# CNC_Power_V2.net
KiCad netlist of a schematic drawn in EAGLE
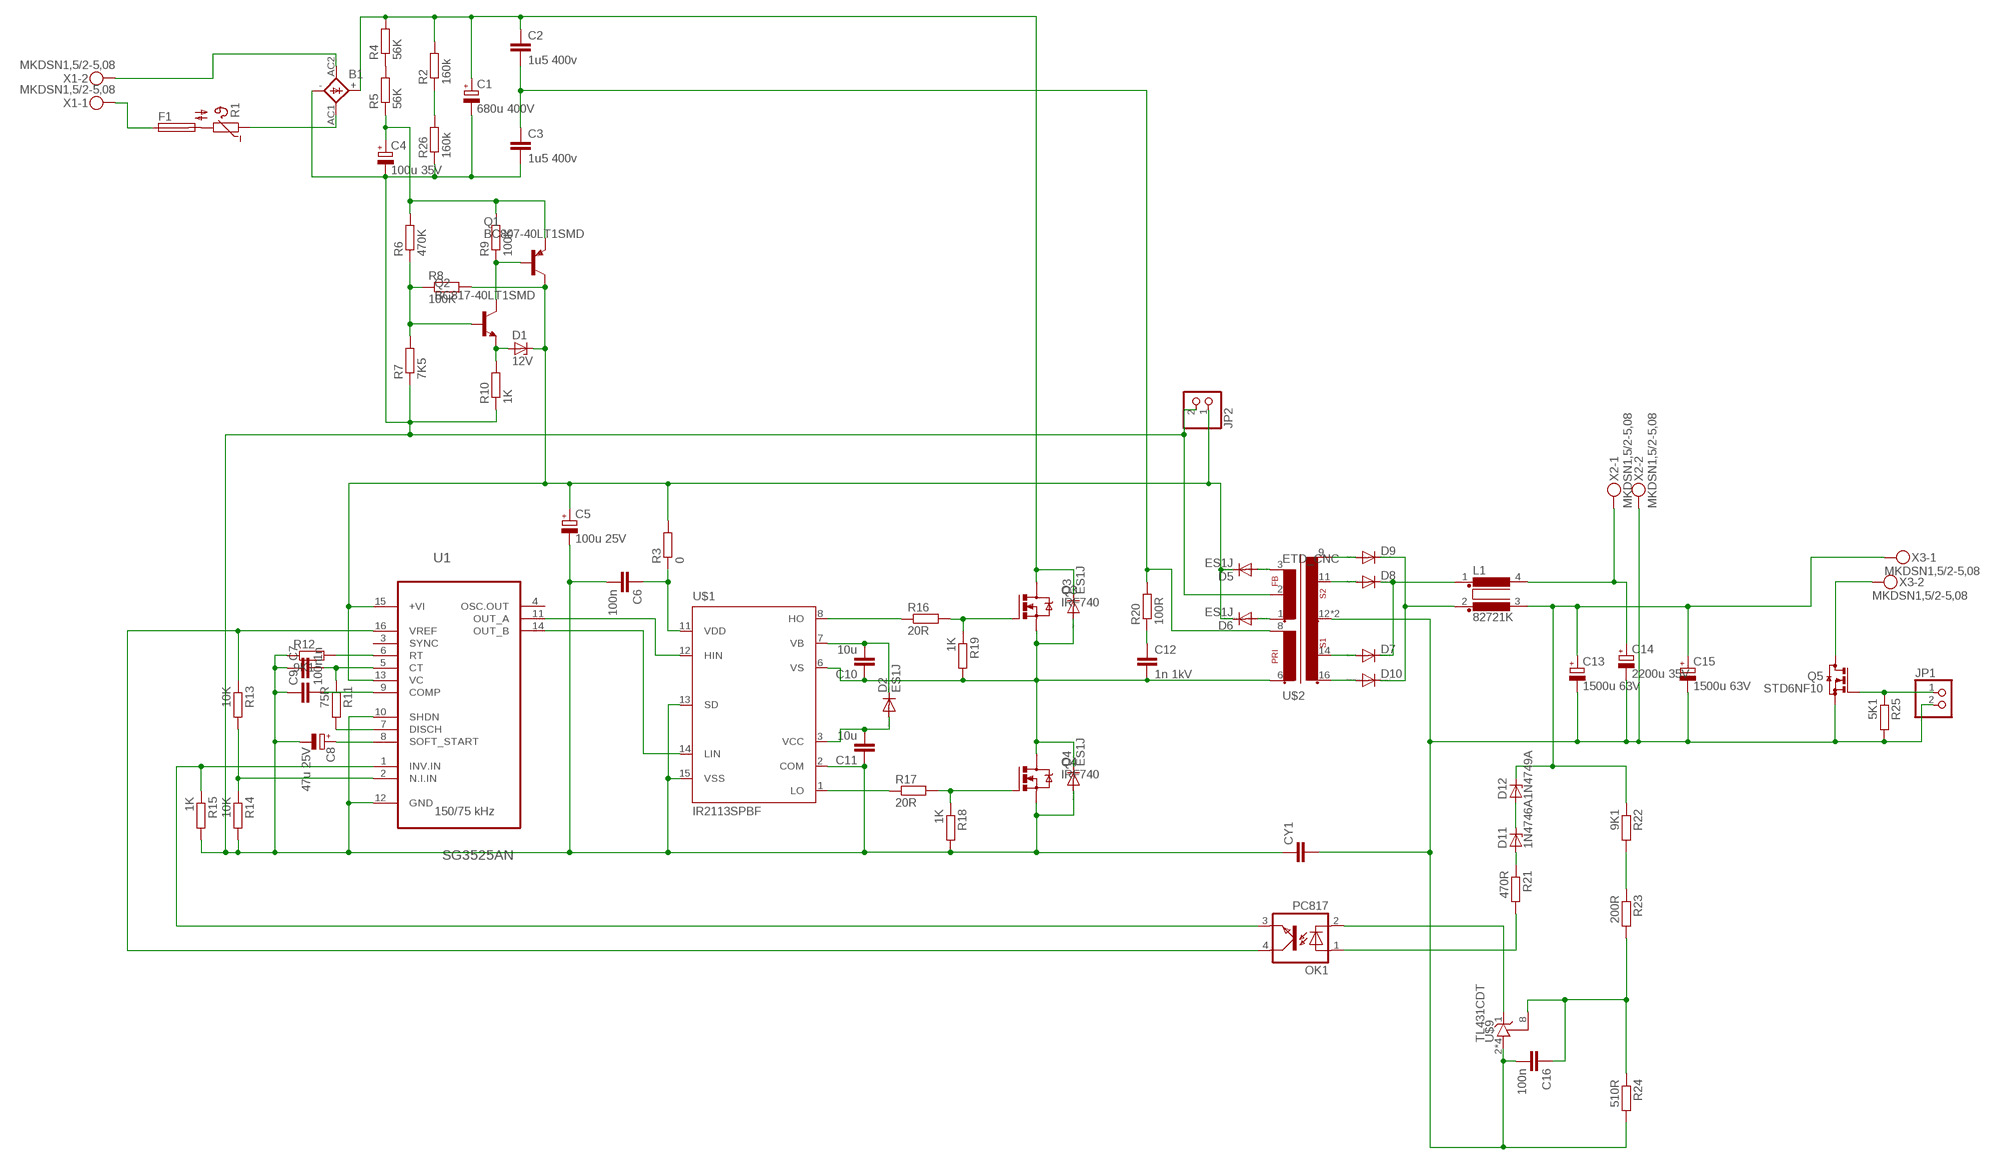
[diagram p0: schematic, sheet 1]

(export (version "E")
  (design (tool "Eeschema 10.0.6"))
  (components
    (comp (ref "B1")
      (value "KBL")
      (footprint "eagle-import:KBL")
      (libsource (lib "eagle-import") (part "KBL"))
    )
    (comp (ref "C1")
      (value "680u 400V")
      (footprint "eagle-import:EB35D")
      (libsource (lib "eagle-import") (part "CPOL-EUE10-35"))
    )
    (comp (ref "C2")
      (value "1u5 400v")
      (footprint "eagle-import:C225-074X268")
      (libsource (lib "eagle-import") (part "C-EU225-074X268"))
    )
    (comp (ref "C3")
      (value "1u5 400v")
      (footprint "eagle-import:C225-074X268")
      (libsource (lib "eagle-import") (part "C-EU225-074X268"))
    )
    (comp (ref "C4")
      (value "100u 35V")
      (footprint "eagle-import:E2,5-7")
      (libsource (lib "eagle-import") (part "CPOL-EUE2.5-7"))
    )
    (comp (ref "C5")
      (value "100u 25V")
      (footprint "eagle-import:E2,5-7")
      (libsource (lib "eagle-import") (part "CPOL-EUE2.5-7"))
    )
    (comp (ref "C6")
      (value "100n")
      (footprint "eagle-import:C0805")
      (libsource (lib "eagle-import") (part "C-EUC0805"))
    )
    (comp (ref "C7")
      (value "1n")
      (footprint "eagle-import:C0805")
      (libsource (lib "eagle-import") (part "C-EUC0805"))
    )
    (comp (ref "C8")
      (value "47u 25V")
      (footprint "eagle-import:E2,5-7")
      (libsource (lib "eagle-import") (part "CPOL-EUE2.5-7"))
    )
    (comp (ref "C9")
      (value "100n")
      (footprint "eagle-import:C0805")
      (libsource (lib "eagle-import") (part "C-EUC0805"))
    )
    (comp (ref "C10")
      (value "10u")
      (footprint "eagle-import:C0805")
      (libsource (lib "eagle-import") (part "C-EUC0805"))
    )
    (comp (ref "C11")
      (value "10u")
      (footprint "eagle-import:C0805")
      (libsource (lib "eagle-import") (part "C-EUC0805"))
    )
    (comp (ref "C12")
      (value "1n 1kV")
      (footprint "eagle-import:C050-025X075")
      (libsource (lib "eagle-import") (part "C-EU050-025X075"))
    )
    (comp (ref "C13")
      (value "1500u 63V")
      (footprint "eagle-import:E7,5-18")
      (libsource (lib "eagle-import") (part "CPOL-EUE7.5-18"))
    )
    (comp (ref "C14")
      (value "2200u 35V")
      (footprint "eagle-import:E7,5-18")
      (libsource (lib "eagle-import") (part "CPOL-EUE7.5-18"))
    )
    (comp (ref "C15")
      (value "1500u 63V")
      (footprint "eagle-import:E7,5-18")
      (libsource (lib "eagle-import") (part "CPOL-EUE7.5-18"))
    )
    (comp (ref "C16")
      (value "100n")
      (footprint "eagle-import:C0805")
      (libsource (lib "eagle-import") (part "C-EUC0805"))
    )
    (comp (ref "CY1")
      (value "CYYC10B4")
      (footprint "eagle-import:YC10B4")
      (libsource (lib "eagle-import") (part "CYYC10B4"))
    )
    (comp (ref "D1")
      (value "12V")
      (footprint "eagle-import:SOD80C")
      (libsource (lib "eagle-import") (part "ZENER-DIODESOD80C"))
    )
    (comp (ref "D2")
      (value "ES1J")
      (footprint "eagle-import:DO214AC")
      (libsource (lib "eagle-import") (part "DIODE-DO214AC"))
    )
    (comp (ref "D3")
      (value "ES1J")
      (footprint "eagle-import:DO214AC")
      (libsource (lib "eagle-import") (part "DIODE-DO214AC"))
    )
    (comp (ref "D4")
      (value "ES1J")
      (footprint "eagle-import:DO214AC")
      (libsource (lib "eagle-import") (part "DIODE-DO214AC"))
    )
    (comp (ref "D5")
      (value "ES1J")
      (footprint "eagle-import:DO214AC")
      (libsource (lib "eagle-import") (part "DIODE-DO214AC"))
    )
    (comp (ref "D6")
      (value "ES1J")
      (footprint "eagle-import:DO214AC")
      (libsource (lib "eagle-import") (part "DIODE-DO214AC"))
    )
    (comp (ref "D7")
      (value "DIODE-DO220S")
      (footprint "eagle-import:DO220S")
      (libsource (lib "eagle-import") (part "DIODE-DO220S"))
    )
    (comp (ref "D8")
      (value "DIODE-DO220S")
      (footprint "eagle-import:DO220S")
      (libsource (lib "eagle-import") (part "DIODE-DO220S"))
    )
    (comp (ref "D9")
      (value "DIODE-DO220S")
      (footprint "eagle-import:DO220S")
      (libsource (lib "eagle-import") (part "DIODE-DO220S"))
    )
    (comp (ref "D10")
      (value "DIODE-DO220S")
      (footprint "eagle-import:DO220S")
      (libsource (lib "eagle-import") (part "DIODE-DO220S"))
    )
    (comp (ref "D11")
      (value "1N4746A")
      (footprint "eagle-import:DO41Z10")
      (libsource (lib "eagle-import") (part "ZENER-DIODEDO41Z10"))
    )
    (comp (ref "D12")
      (value "1N4749A")
      (footprint "eagle-import:DO41Z10")
      (libsource (lib "eagle-import") (part "ZENER-DIODEDO41Z10"))
    )
    (comp (ref "F1")
      (value "SH22,5")
      (footprint "eagle-import:SH22,5")
      (fields (field (name "MF") "SCHURTER") (field (name "MPN") "0031.8201"))
      (libsource (lib "eagle-import") (part "SH22,5"))
    )
    (comp (ref "JP1")
      (value "PINHD-1X2")
      (footprint "eagle-import:1X02")
      (libsource (lib "eagle-import") (part "PINHD-1X2"))
    )
    (comp (ref "JP2")
      (value "PINHD-1X2")
      (footprint "eagle-import:1X02")
      (libsource (lib "eagle-import") (part "PINHD-1X2"))
    )
    (comp (ref "L1")
      (value "82721K")
      (footprint "eagle-import:82721K")
      (libsource (lib "eagle-import") (part "82721K"))
    )
    (comp (ref "OK1")
      (value "PC817")
      (footprint "eagle-import:DIL04")
      (fields (field (name "MPN") "PC817X4J000F"))
      (libsource (lib "eagle-import") (part "PC817"))
    )
    (comp (ref "Q1")
      (value "BC807-40LT1SMD")
      (footprint "eagle-import:SOT23-BEC")
      (libsource (lib "eagle-import") (part "BC807SMD-40LT1"))
    )
    (comp (ref "Q2")
      (value "BC817-40LT1SMD")
      (footprint "eagle-import:SOT23-BEC")
      (libsource (lib "eagle-import") (part "BC817SMD-40LT1"))
    )
    (comp (ref "Q3")
      (value "IRF740")
      (footprint "eagle-import:TO220BV")
      (libsource (lib "eagle-import") (part "IRF740"))
    )
    (comp (ref "Q4")
      (value "IRF740")
      (footprint "eagle-import:TO220BV")
      (libsource (lib "eagle-import") (part "IRF740"))
    )
    (comp (ref "Q5")
      (value "STD6NF10")
      (footprint "eagle-import:DPAK")
      (libsource (lib "eagle-import") (part "STD6NF10"))
    )
    (comp (ref "R1")
      (value "B57164")
      (footprint "eagle-import:B57164")
      (fields (field (name "MPN") "B57164K474K52"))
      (libsource (lib "eagle-import") (part "B57164"))
    )
    (comp (ref "R2")
      (value "160k")
      (footprint "eagle-import:0207_10")
      (libsource (lib "eagle-import") (part "R-EU_0207/10"))
    )
    (comp (ref "R3")
      (value "0")
      (footprint "eagle-import:R1206")
      (libsource (lib "eagle-import") (part "R-EU_R1206"))
    )
    (comp (ref "R4")
      (value "56K")
      (footprint "eagle-import:0617_17")
      (libsource (lib "eagle-import") (part "R-EU_0617/17"))
    )
    (comp (ref "R5")
      (value "56K")
      (footprint "eagle-import:0617_17")
      (libsource (lib "eagle-import") (part "R-EU_0617/17"))
    )
    (comp (ref "R6")
      (value "470K")
      (footprint "eagle-import:R0805")
      (libsource (lib "eagle-import") (part "R-EU_R0805"))
    )
    (comp (ref "R7")
      (value "7K5")
      (footprint "eagle-import:R0805")
      (libsource (lib "eagle-import") (part "R-EU_R0805"))
    )
    (comp (ref "R8")
      (value "100K")
      (footprint "eagle-import:R0805")
      (libsource (lib "eagle-import") (part "R-EU_R0805"))
    )
    (comp (ref "R9")
      (value "100K")
      (footprint "eagle-import:R0805")
      (libsource (lib "eagle-import") (part "R-EU_R0805"))
    )
    (comp (ref "R10")
      (value "1K")
      (footprint "eagle-import:R0805")
      (libsource (lib "eagle-import") (part "R-EU_R0805"))
    )
    (comp (ref "R11")
      (value "75R")
      (footprint "eagle-import:R0805")
      (libsource (lib "eagle-import") (part "R-EU_R0805"))
    )
    (comp (ref "R12")
      (value "9K1")
      (footprint "eagle-import:R0805")
      (libsource (lib "eagle-import") (part "R-EU_R0805"))
    )
    (comp (ref "R13")
      (value "10K")
      (footprint "eagle-import:R0805")
      (libsource (lib "eagle-import") (part "R-EU_R0805"))
    )
    (comp (ref "R14")
      (value "10K")
      (footprint "eagle-import:R0805")
      (libsource (lib "eagle-import") (part "R-EU_R0805"))
    )
    (comp (ref "R15")
      (value "1K")
      (footprint "eagle-import:R0805")
      (libsource (lib "eagle-import") (part "R-EU_R0805"))
    )
    (comp (ref "R16")
      (value "20R")
      (footprint "eagle-import:R1206")
      (libsource (lib "eagle-import") (part "R-EU_R1206"))
    )
    (comp (ref "R17")
      (value "20R")
      (footprint "eagle-import:R1206")
      (libsource (lib "eagle-import") (part "R-EU_R1206"))
    )
    (comp (ref "R18")
      (value "1K")
      (footprint "eagle-import:R0805")
      (libsource (lib "eagle-import") (part "R-EU_R0805"))
    )
    (comp (ref "R19")
      (value "1K")
      (footprint "eagle-import:R0805")
      (libsource (lib "eagle-import") (part "R-EU_R0805"))
    )
    (comp (ref "R20")
      (value "100R")
      (footprint "eagle-import:0617_17")
      (libsource (lib "eagle-import") (part "R-EU_0617/17"))
    )
    (comp (ref "R21")
      (value "470R")
      (footprint "eagle-import:R0805")
      (libsource (lib "eagle-import") (part "R-EU_R0805"))
    )
    (comp (ref "R22")
      (value "9K1")
      (footprint "eagle-import:R0805")
      (libsource (lib "eagle-import") (part "R-EU_R0805"))
    )
    (comp (ref "R23")
      (value "200R")
      (footprint "eagle-import:R0805")
      (libsource (lib "eagle-import") (part "R-EU_R0805"))
    )
    (comp (ref "R24")
      (value "510R")
      (footprint "eagle-import:R0805")
      (libsource (lib "eagle-import") (part "R-EU_R0805"))
    )
    (comp (ref "R25")
      (value "5K1")
      (footprint "eagle-import:R0805")
      (libsource (lib "eagle-import") (part "R-EU_R0805"))
    )
    (comp (ref "R26")
      (value "160k")
      (footprint "eagle-import:0207_10")
      (libsource (lib "eagle-import") (part "R-EU_0207/10"))
    )
    (comp (ref "U$1")
      (value "IR2113SPBF")
      (footprint "eagle-import:SO16W")
      (libsource (lib "eagle-import") (part "IR2113SPBF"))
    )
    (comp (ref "U$2")
      (value "ETD_CNC")
      (footprint "eagle-import:ETD39_16PIN")
      (libsource (lib "eagle-import") (part "ETD_CNC"))
    )
    (comp (ref "U$9")
      (value "TL431CDT")
      (footprint "eagle-import:SO8")
      (libsource (lib "eagle-import") (part "TL431CDT"))
    )
    (comp (ref "U1")
      (value "SG3525AN")
      (footprint "eagle-import:DIP254P762X510-16")
      (libsource (lib "eagle-import") (part "SG3525AN"))
    )
    (comp (ref "X1")
      (value "MKDSN1,5/2-5,08")
      (footprint "eagle-import:MKDSN1,5_2-5,08")
      (libsource (lib "eagle-import") (part "MKDSN1,5/2-5,08"))
    )
    (comp (ref "X2")
      (value "MKDSN1,5/2-5,08")
      (footprint "eagle-import:MKDSN1,5_2-5,08")
      (libsource (lib "eagle-import") (part "MKDSN1,5/2-5,08"))
    )
    (comp (ref "X3")
      (value "MKDSN1,5/2-5,08")
      (footprint "eagle-import:MKDSN1,5_2-5,08")
      (libsource (lib "eagle-import") (part "MKDSN1,5/2-5,08"))
    )
  )
  (nets
    (net (code "1") (name "Net-(B1-AC1)") (class "Default")
      (node (ref "B1") (pin "AC2") (pinfunction "AC1_AC2") (pintype "passive"))
      (node (ref "X1") (pin "2") (pinfunction "KL_2") (pintype "passive"))
    )
    (net (code "2") (name "Net-(B1-AC2)") (class "Default")
      (node (ref "B1") (pin "AC1") (pinfunction "AC2_AC1") (pintype "passive"))
      (node (ref "R1") (pin "1") (pinfunction "1_1") (pintype "passive"))
    )
    (net (code "3") (name "Net-(B1-Pad+)") (class "Default")
      (node (ref "B1") (pin "+") (pinfunction "+_+") (pintype "passive"))
      (node (ref "C1") (pin "+") (pinfunction "+_+") (pintype "passive"))
      (node (ref "C2") (pin "1") (pinfunction "1_1") (pintype "passive"))
      (node (ref "D3") (pin "C") (pinfunction "C_C") (pintype "passive"))
      (node (ref "Q3") (pin "D") (pinfunction "D_D") (pintype "passive"))
      (node (ref "R2") (pin "2") (pinfunction "2_2") (pintype "passive"))
      (node (ref "R4") (pin "2") (pinfunction "2_2") (pintype "passive"))
    )
    (net (code "4") (name "Net-(C4-Pad+)") (class "Default")
      (node (ref "C4") (pin "+") (pinfunction "+_+") (pintype "passive"))
      (node (ref "Q1") (pin "E") (pinfunction "E_E") (pintype "passive"))
      (node (ref "R5") (pin "1") (pinfunction "1_1") (pintype "passive"))
      (node (ref "R6") (pin "2") (pinfunction "2_2") (pintype "passive"))
      (node (ref "R9") (pin "2") (pinfunction "2_2") (pintype "passive"))
    )
    (net (code "5") (name "Net-(C12-Pad1)") (class "Default")
      (node (ref "C12") (pin "1") (pinfunction "1_1") (pintype "passive"))
      (node (ref "R20") (pin "1") (pinfunction "1_1") (pintype "passive"))
    )
    (net (code "6") (name "Net-(D1-PadA)") (class "Default")
      (node (ref "D1") (pin "A") (pinfunction "A_A") (pintype "passive"))
      (node (ref "Q2") (pin "E") (pinfunction "E_E") (pintype "passive"))
      (node (ref "R10") (pin "2") (pinfunction "2_2") (pintype "passive"))
    )
    (net (code "7") (name "Net-(D7-PadC)") (class "Default")
      (node (ref "D7") (pin "C") (pinfunction "C_C") (pintype "passive"))
      (node (ref "D8") (pin "C") (pinfunction "C_C") (pintype "passive"))
      (node (ref "L1") (pin "1") (pinfunction "1_1") (pintype "passive"))
    )
    (net (code "8") (name "Net-(D11-PadA)") (class "Default")
      (node (ref "D11") (pin "A") (pinfunction "A_A") (pintype "passive"))
      (node (ref "R21") (pin "1") (pinfunction "1_1") (pintype "passive"))
    )
    (net (code "9") (name "Net-(D11-PadC)") (class "Default")
      (node (ref "D11") (pin "C") (pinfunction "C_C") (pintype "passive"))
      (node (ref "D12") (pin "A") (pinfunction "A_A") (pintype "passive"))
    )
    (net (code "10") (name "Net-(F1-Pad2)") (class "Default")
      (node (ref "F1") (pin "2") (pinfunction "2_2") (pintype "passive"))
      (node (ref "R1") (pin "2") (pinfunction "2_2") (pintype "passive"))
    )
    (net (code "11") (name "Net-(JP1-Pad1)") (class "Default")
      (node (ref "JP1") (pin "1") (pinfunction "1_1") (pintype "passive"))
      (node (ref "Q5") (pin "G") (pinfunction "G_G") (pintype "passive"))
      (node (ref "R25") (pin "1") (pinfunction "1_1") (pintype "passive"))
    )
    (net (code "12") (name "Net-(L1-2)") (class "Default")
      (node (ref "C14") (pin "+") (pinfunction "+_+") (pintype "passive"))
      (node (ref "L1") (pin "4") (pinfunction "2_4") (pintype "passive"))
      (node (ref "X2") (pin "1") (pinfunction "KL_1") (pintype "passive"))
    )
    (net (code "13") (name "Net-(L1-3)") (class "Default")
      (node (ref "D10") (pin "C") (pinfunction "C_C") (pintype "passive"))
      (node (ref "D9") (pin "C") (pinfunction "C_C") (pintype "passive"))
      (node (ref "L1") (pin "2") (pinfunction "3_2") (pintype "passive"))
    )
    (net (code "14") (name "Net-(L1-4)") (class "Default")
      (node (ref "C13") (pin "+") (pinfunction "+_+") (pintype "passive"))
      (node (ref "C15") (pin "+") (pinfunction "+_+") (pintype "passive"))
      (node (ref "D12") (pin "C") (pinfunction "C_C") (pintype "passive"))
      (node (ref "L1") (pin "3") (pinfunction "4_3") (pintype "passive"))
      (node (ref "R22") (pin "1") (pinfunction "1_1") (pintype "passive"))
      (node (ref "X3") (pin "1") (pinfunction "KL_1") (pintype "passive"))
    )
    (net (code "15") (name "Net-(OK1-A)") (class "Default")
      (node (ref "OK1") (pin "1") (pinfunction "A_1") (pintype "passive"))
      (node (ref "R21") (pin "2") (pinfunction "2_2") (pintype "passive"))
    )
    (net (code "16") (name "Net-(OK1-C)") (class "Default")
      (node (ref "OK1") (pin "2") (pinfunction "C_2") (pintype "passive"))
      (node (ref "U$9") (pin "1") (pinfunction "C_1") (pintype "passive"))
    )
    (net (code "17") (name "Net-(OK1-COL)") (class "Default")
      (node (ref "OK1") (pin "4") (pinfunction "COL_4") (pintype "passive"))
      (node (ref "R13") (pin "1") (pinfunction "1_1") (pintype "passive"))
      (node (ref "U1") (pin "16") (pinfunction "VREF_16") (pintype "passive"))
    )
    (net (code "18") (name "Net-(OK1-EMIT)") (class "Default")
      (node (ref "OK1") (pin "3") (pinfunction "EMIT_3") (pintype "passive"))
      (node (ref "R15") (pin "1") (pinfunction "1_1") (pintype "passive"))
      (node (ref "U1") (pin "1") (pinfunction "INV.IN_1") (pintype "input"))
    )
    (net (code "19") (name "Net-(Q1-PadB)") (class "Default")
      (node (ref "Q1") (pin "B") (pinfunction "B_B") (pintype "passive"))
      (node (ref "Q2") (pin "C") (pinfunction "C_C") (pintype "passive"))
      (node (ref "R9") (pin "1") (pinfunction "1_1") (pintype "passive"))
    )
    (net (code "20") (name "Net-(Q2-PadB)") (class "Default")
      (node (ref "Q2") (pin "B") (pinfunction "B_B") (pintype "passive"))
      (node (ref "R6") (pin "1") (pinfunction "1_1") (pintype "passive"))
      (node (ref "R7") (pin "2") (pinfunction "2_2") (pintype "passive"))
      (node (ref "R8") (pin "1") (pinfunction "1_1") (pintype "passive"))
    )
    (net (code "21") (name "Net-(Q3-PadG)") (class "Default")
      (node (ref "Q3") (pin "G") (pinfunction "G_G") (pintype "passive"))
      (node (ref "R16") (pin "2") (pinfunction "2_2") (pintype "passive"))
      (node (ref "R19") (pin "1") (pinfunction "1_1") (pintype "passive"))
    )
    (net (code "22") (name "Net-(Q4-PadG)") (class "Default")
      (node (ref "Q4") (pin "G") (pinfunction "G_G") (pintype "passive"))
      (node (ref "R17") (pin "2") (pinfunction "2_2") (pintype "passive"))
      (node (ref "R18") (pin "1") (pinfunction "1_1") (pintype "passive"))
    )
    (net (code "23") (name "Net-(R2-Pad1)") (class "Default")
      (node (ref "R2") (pin "1") (pinfunction "1_1") (pintype "passive"))
      (node (ref "R26") (pin "2") (pinfunction "2_2") (pintype "passive"))
    )
    (net (code "24") (name "Net-(R4-Pad1)") (class "Default")
      (node (ref "R4") (pin "1") (pinfunction "1_1") (pintype "passive"))
      (node (ref "R5") (pin "2") (pinfunction "2_2") (pintype "passive"))
    )
    (net (code "25") (name "Net-(R22-Pad2)") (class "Default")
      (node (ref "R22") (pin "2") (pinfunction "2_2") (pintype "passive"))
      (node (ref "R23") (pin "1") (pinfunction "1_1") (pintype "passive"))
    )
    (net (code "26") (name "Net-(U$1-COM)") (class "Default")
      (node (ref "B1") (pin "-") (pinfunction "-_-") (pintype "passive"))
      (node (ref "C1") (pin "-") (pinfunction "-_-") (pintype "passive"))
      (node (ref "C11") (pin "1") (pinfunction "1_1") (pintype "passive"))
      (node (ref "C3") (pin "2") (pinfunction "2_2") (pintype "passive"))
      (node (ref "C4") (pin "-") (pinfunction "-_-") (pintype "passive"))
      (node (ref "C5") (pin "-") (pinfunction "-_-") (pintype "passive"))
      (node (ref "C6") (pin "2") (pinfunction "2_2") (pintype "passive"))
      (node (ref "C7") (pin "1") (pinfunction "1_1") (pintype "passive"))
      (node (ref "C8") (pin "-") (pinfunction "-_-") (pintype "passive"))
      (node (ref "C9") (pin "1") (pinfunction "1_1") (pintype "passive"))
      (node (ref "CY1") (pin "1") (pinfunction "1_1") (pintype "passive"))
      (node (ref "D4") (pin "A") (pinfunction "A_A") (pintype "passive"))
      (node (ref "JP2") (pin "2") (pinfunction "2_2") (pintype "passive"))
      (node (ref "Q4") (pin "S") (pinfunction "S_S") (pintype "passive"))
      (node (ref "R10") (pin "1") (pinfunction "1_1") (pintype "passive"))
      (node (ref "R12") (pin "1") (pinfunction "1_1") (pintype "passive"))
      (node (ref "R14") (pin "2") (pinfunction "2_2") (pintype "passive"))
      (node (ref "R15") (pin "2") (pinfunction "2_2") (pintype "passive"))
      (node (ref "R18") (pin "2") (pinfunction "2_2") (pintype "passive"))
      (node (ref "R26") (pin "1") (pinfunction "1_1") (pintype "passive"))
      (node (ref "R7") (pin "1") (pinfunction "1_1") (pintype "passive"))
      (node (ref "U$1") (pin "13") (pinfunction "SD_13") (pintype "input"))
      (node (ref "U$1") (pin "15") (pinfunction "VSS_15") (pintype "power_in"))
      (node (ref "U$1") (pin "2") (pinfunction "COM_2") (pintype "power_in"))
      (node (ref "U$2") (pin "2") (pinfunction "F0_2") (pintype "passive"))
      (node (ref "U1") (pin "10") (pinfunction "SHDN_10") (pintype "input"))
      (node (ref "U1") (pin "12") (pinfunction "GND_12") (pintype "passive"))
    )
    (net (code "27") (name "Net-(U$1-HIN)") (class "Default")
      (node (ref "U$1") (pin "12") (pinfunction "HIN_12") (pintype "input"))
      (node (ref "U1") (pin "11") (pinfunction "OUT_A_11") (pintype "output"))
    )
    (net (code "28") (name "Net-(U$1-HO)") (class "Default")
      (node (ref "R16") (pin "1") (pinfunction "1_1") (pintype "passive"))
      (node (ref "U$1") (pin "8") (pinfunction "HO_8") (pintype "output"))
    )
    (net (code "29") (name "Net-(U$1-LIN)") (class "Default")
      (node (ref "U$1") (pin "14") (pinfunction "LIN_14") (pintype "input"))
      (node (ref "U1") (pin "14") (pinfunction "OUT_B_14") (pintype "output"))
    )
    (net (code "30") (name "Net-(U$1-LO)") (class "Default")
      (node (ref "R17") (pin "1") (pinfunction "1_1") (pintype "passive"))
      (node (ref "U$1") (pin "1") (pinfunction "LO_1") (pintype "output"))
    )
    (net (code "31") (name "Net-(U$1-VB)") (class "Default")
      (node (ref "C10") (pin "2") (pinfunction "2_2") (pintype "passive"))
      (node (ref "D2") (pin "C") (pinfunction "C_C") (pintype "passive"))
      (node (ref "U$1") (pin "7") (pinfunction "VB_7") (pintype "power_in"))
    )
    (net (code "32") (name "Net-(U$1-VCC)") (class "Default")
      (node (ref "C11") (pin "2") (pinfunction "2_2") (pintype "passive"))
      (node (ref "D2") (pin "A") (pinfunction "A_A") (pintype "passive"))
      (node (ref "U$1") (pin "3") (pinfunction "VCC_3") (pintype "power_in"))
    )
    (net (code "33") (name "Net-(U$1-VDD)") (class "Default")
      (node (ref "C6") (pin "1") (pinfunction "1_1") (pintype "passive"))
      (node (ref "R3") (pin "1") (pinfunction "1_1") (pintype "passive"))
      (node (ref "U$1") (pin "11") (pinfunction "VDD_11") (pintype "power_in"))
    )
    (net (code "34") (name "Net-(U$1-VS)") (class "Default")
      (node (ref "C10") (pin "1") (pinfunction "1_1") (pintype "passive"))
      (node (ref "C12") (pin "2") (pinfunction "2_2") (pintype "passive"))
      (node (ref "D3") (pin "A") (pinfunction "A_A") (pintype "passive"))
      (node (ref "D4") (pin "C") (pinfunction "C_C") (pintype "passive"))
      (node (ref "Q3") (pin "S") (pinfunction "S_S") (pintype "passive"))
      (node (ref "Q4") (pin "D") (pinfunction "D_D") (pintype "passive"))
      (node (ref "R19") (pin "2") (pinfunction "2_2") (pintype "passive"))
      (node (ref "U$1") (pin "6") (pinfunction "VS_6") (pintype "power_in"))
      (node (ref "U$2") (pin "6") (pinfunction "P-1_6") (pintype "passive"))
    )
    (net (code "35") (name "Net-(U$2-F+12)") (class "Default")
      (node (ref "D6") (pin "A") (pinfunction "A_A") (pintype "passive"))
      (node (ref "U$2") (pin "1") (pinfunction "F+12_1") (pintype "passive"))
    )
    (net (code "36") (name "Net-(U$2-F-12)") (class "Default")
      (node (ref "D5") (pin "A") (pinfunction "A_A") (pintype "passive"))
      (node (ref "U$2") (pin "3") (pinfunction "F-12_3") (pintype "passive"))
    )
    (net (code "37") (name "Net-(U$2-P-2)") (class "Default")
      (node (ref "C2") (pin "2") (pinfunction "2_2") (pintype "passive"))
      (node (ref "C3") (pin "1") (pinfunction "1_1") (pintype "passive"))
      (node (ref "R20") (pin "2") (pinfunction "2_2") (pintype "passive"))
      (node (ref "U$2") (pin "8") (pinfunction "P-2_8") (pintype "passive"))
    )
    (net (code "38") (name "Net-(U$2-S-24)") (class "Default")
      (node (ref "D8") (pin "A") (pinfunction "A_A") (pintype "passive"))
      (node (ref "U$2") (pin "11") (pinfunction "S-24_11") (pintype "passive"))
    )
    (net (code "39") (name "Net-(U$2-S-48)") (class "Default")
      (node (ref "D9") (pin "A") (pinfunction "A_A") (pintype "passive"))
      (node (ref "U$2") (pin "9") (pinfunction "S-48_9") (pintype "passive"))
    )
    (net (code "40") (name "Net-(U$2-S1+24)") (class "Default")
      (node (ref "D7") (pin "A") (pinfunction "A_A") (pintype "passive"))
      (node (ref "U$2") (pin "14") (pinfunction "S1+24_14") (pintype "passive"))
    )
    (net (code "41") (name "Net-(U$2-S1+48)") (class "Default")
      (node (ref "D10") (pin "A") (pinfunction "A_A") (pintype "passive"))
      (node (ref "U$2") (pin "16") (pinfunction "S1+48_16") (pintype "passive"))
    )
    (net (code "42") (name "Net-(U$9-R)") (class "Default")
      (node (ref "C16") (pin "1") (pinfunction "1_1") (pintype "passive"))
      (node (ref "R23") (pin "2") (pinfunction "2_2") (pintype "passive"))
      (node (ref "R24") (pin "1") (pinfunction "1_1") (pintype "passive"))
      (node (ref "U$9") (pin "8") (pinfunction "R_8") (pintype "passive"))
    )
    (net (code "43") (name "Net-(U1-+VI)") (class "Default")
      (node (ref "C5") (pin "+") (pinfunction "+_+") (pintype "passive"))
      (node (ref "D1") (pin "C") (pinfunction "C_C") (pintype "passive"))
      (node (ref "D5") (pin "C") (pinfunction "C_C") (pintype "passive"))
      (node (ref "D6") (pin "C") (pinfunction "C_C") (pintype "passive"))
      (node (ref "JP2") (pin "1") (pinfunction "1_1") (pintype "passive"))
      (node (ref "Q1") (pin "C") (pinfunction "C_C") (pintype "passive"))
      (node (ref "R3") (pin "2") (pinfunction "2_2") (pintype "passive"))
      (node (ref "R8") (pin "2") (pinfunction "2_2") (pintype "passive"))
      (node (ref "U1") (pin "13") (pinfunction "VC_13") (pintype "passive"))
      (node (ref "U1") (pin "15") (pinfunction "+VI_15") (pintype "power_in"))
    )
    (net (code "44") (name "Net-(U1-COMP)") (class "Default")
      (node (ref "C9") (pin "2") (pinfunction "2_2") (pintype "passive"))
      (node (ref "U1") (pin "9") (pinfunction "COMP_9") (pintype "passive"))
    )
    (net (code "45") (name "Net-(U1-CT)") (class "Default")
      (node (ref "C7") (pin "2") (pinfunction "2_2") (pintype "passive"))
      (node (ref "R11") (pin "1") (pinfunction "1_1") (pintype "passive"))
      (node (ref "U1") (pin "5") (pinfunction "CT_5") (pintype "passive"))
    )
    (net (code "46") (name "Net-(U1-DISCH)") (class "Default")
      (node (ref "R11") (pin "2") (pinfunction "2_2") (pintype "passive"))
      (node (ref "U1") (pin "7") (pinfunction "DISCH_7") (pintype "passive"))
    )
    (net (code "47") (name "Net-(U1-N.I.IN)") (class "Default")
      (node (ref "R13") (pin "2") (pinfunction "2_2") (pintype "passive"))
      (node (ref "R14") (pin "1") (pinfunction "1_1") (pintype "passive"))
      (node (ref "U1") (pin "2") (pinfunction "N.I.IN_2") (pintype "input"))
    )
    (net (code "48") (name "Net-(U1-RT)") (class "Default")
      (node (ref "R12") (pin "2") (pinfunction "2_2") (pintype "passive"))
      (node (ref "U1") (pin "6") (pinfunction "RT_6") (pintype "passive"))
    )
    (net (code "49") (name "Net-(U1-SOFT_START)") (class "Default")
      (node (ref "C8") (pin "+") (pinfunction "+_+") (pintype "passive"))
      (node (ref "U1") (pin "8") (pinfunction "SOFT_START_8") (pintype "passive"))
    )
    (net (code "50") (name "Net-(X1A-KL)") (class "Default")
      (node (ref "F1") (pin "1") (pinfunction "1_1") (pintype "passive"))
      (node (ref "X1") (pin "1") (pinfunction "KL_1") (pintype "passive"))
    )
    (net (code "51") (name "Net-(X2B-KL)") (class "Default")
      (node (ref "C13") (pin "-") (pinfunction "-_-") (pintype "passive"))
      (node (ref "C14") (pin "-") (pinfunction "-_-") (pintype "passive"))
      (node (ref "C15") (pin "-") (pinfunction "-_-") (pintype "passive"))
      (node (ref "C16") (pin "2") (pinfunction "2_2") (pintype "passive"))
      (node (ref "CY1") (pin "2") (pinfunction "2_2") (pintype "passive"))
      (node (ref "JP1") (pin "2") (pinfunction "2_2") (pintype "passive"))
      (node (ref "Q5") (pin "S") (pinfunction "S_S") (pintype "passive"))
      (node (ref "R24") (pin "2") (pinfunction "2_2") (pintype "passive"))
      (node (ref "R25") (pin "2") (pinfunction "2_2") (pintype "passive"))
      (node (ref "U$2") (pin "12") (pinfunction "S-0_12") (pintype "passive"))
      (node (ref "U$2") (pin "13") (pinfunction "S-0_13") (pintype "passive"))
      (node (ref "U$9") (pin "2") (pinfunction "A_2") (pintype "passive"))
      (node (ref "U$9") (pin "3") (pinfunction "A_3") (pintype "passive"))
      (node (ref "U$9") (pin "6") (pinfunction "A_6") (pintype "passive"))
      (node (ref "U$9") (pin "7") (pinfunction "A_7") (pintype "passive"))
      (node (ref "X2") (pin "2") (pinfunction "KL_2") (pintype "passive"))
    )
    (net (code "52") (name "Net-(X3B-KL)") (class "Default")
      (node (ref "Q5") (pin "D") (pinfunction "D_D") (pintype "passive"))
      (node (ref "X3") (pin "2") (pinfunction "KL_2") (pintype "passive"))
    )
    (net (code "53") (name "unconnected-(U1-OSC.OUT-Pad4)") (class "Default")
      (node (ref "U1") (pin "4") (pinfunction "OSC.OUT_4") (pintype "output"))
    )
    (net (code "54") (name "unconnected-(U1-SYNC-Pad3)") (class "Default")
      (node (ref "U1") (pin "3") (pinfunction "SYNC_3") (pintype "passive"))
    )
  )
)
